# Sheet1.net
KiCad netlist of a schematic drawn in Altium Designer
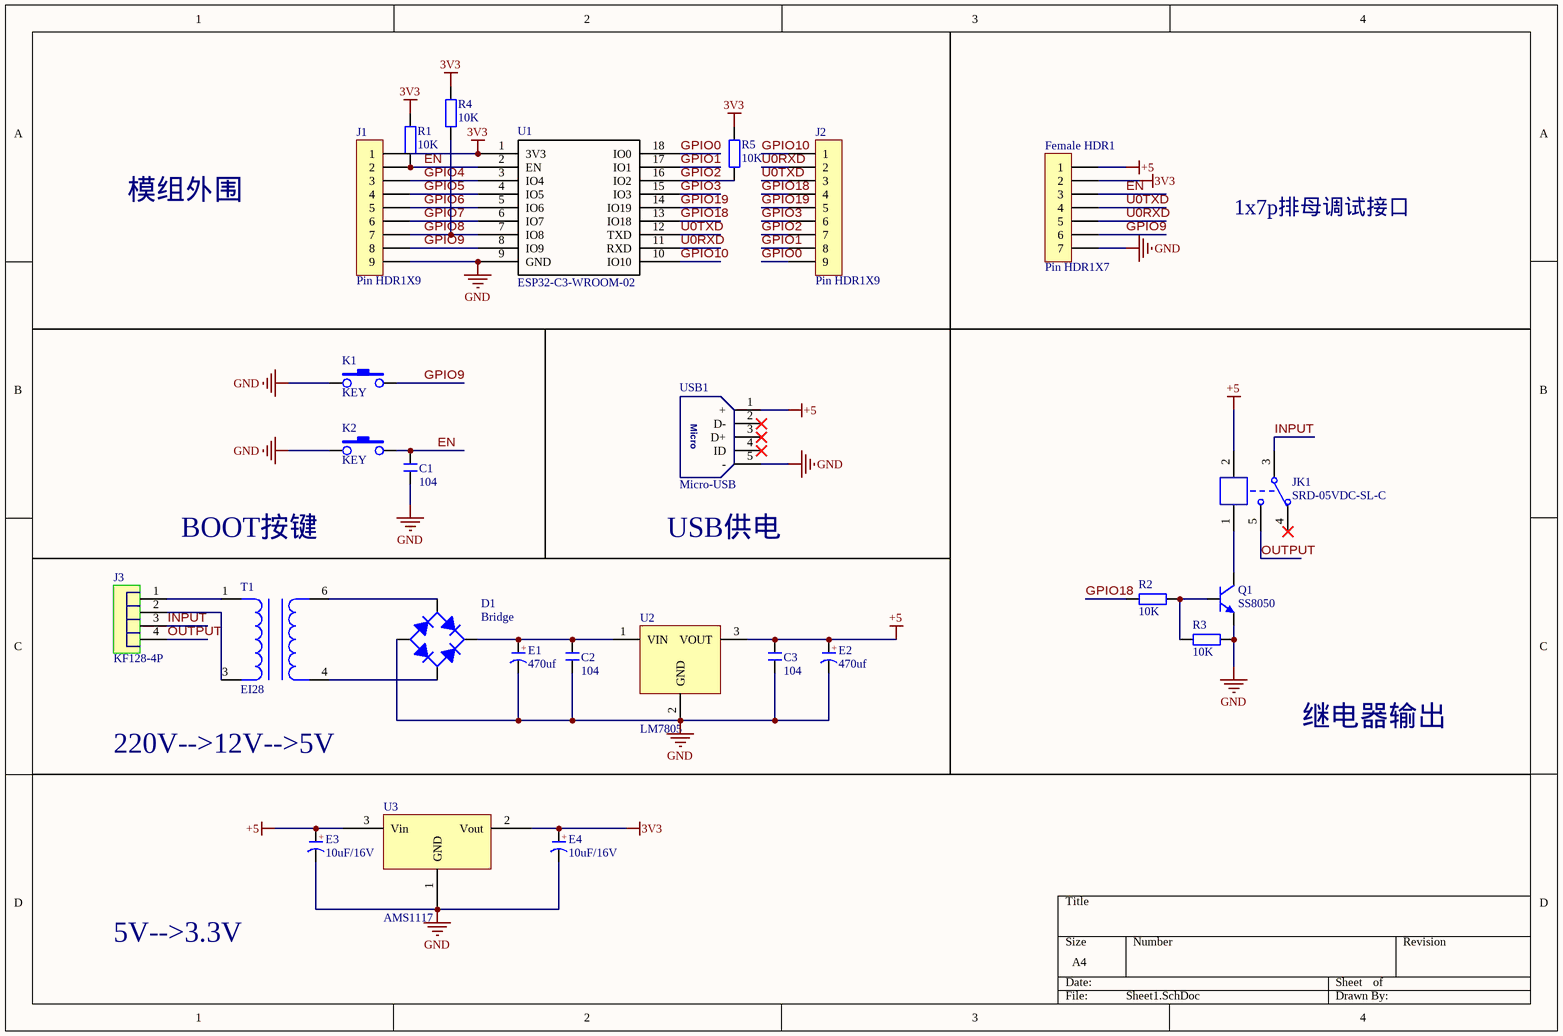
[diagram p0: Sheet1.SchDoc]

(export (version "E")
  (design (tool "Eeschema 10.0.6"))
  (components
    (comp (ref "C1")
      (value "104")
      (footprint "CC 1.8*3.6")
      (description "直插瓷片电容")
      (fields (field (name "版权归属") "源创客"))
      (libsource (lib "3.1   - 电阻-电容-电感") (part "C-CC"))
    )
    (comp (ref "C2")
      (value "104")
      (footprint "CC 1.8*3.6")
      (description "直插瓷片电容")
      (fields (field (name "版权归属") "源创客"))
      (libsource (lib "3.1   - 电阻-电容-电感") (part "C-CC"))
    )
    (comp (ref "C3")
      (value "104")
      (footprint "CC 1.8*3.6")
      (description "直插瓷片电容")
      (fields (field (name "版权归属") "源创客"))
      (libsource (lib "3.1   - 电阻-电容-电感") (part "C-CC"))
    )
    (comp (ref "D1") (value "Bridge") (footprint "GBP") (libsource (lib "IOT_light") (part "Bridge")))
    (comp (ref "E1")
      (value "470uf")
      (footprint "CAP 1.5*4*8")
      (description "直插电解电容")
      (fields (field (name "版权归属") "源创客"))
      (libsource (lib "3.1   - 电阻-电容-电感") (part "C-CAP"))
    )
    (comp (ref "E2")
      (value "470uf")
      (footprint "CAP 1.5*4*8")
      (description "直插电解电容")
      (fields (field (name "版权归属") "源创客"))
      (libsource (lib "3.1   - 电阻-电容-电感") (part "C-CAP"))
    )
    (comp (ref "E3")
      (value "10uF/16V")
      (footprint "CAP 1.5*4*8")
      (description "直插电解电容")
      (fields (field (name "版权归属") "源创客"))
      (libsource (lib "3.1   - 电阻-电容-电感") (part "C-CAP"))
    )
    (comp (ref "E4")
      (value "10uF/16V")
      (footprint "CAP 1.5*4*8")
      (description "直插电解电容")
      (fields (field (name "版权归属") "源创客"))
      (libsource (lib "3.1   - 电阻-电容-电感") (part "C-CAP"))
    )
    (comp (ref "Female HDR1")
      (value "Pin HDR1X7")
      (footprint "Pin HDR1X7/2.54mm-W")
      (libsource (lib "IOT_light") (part "Pin HDR1X7"))
    )
    (comp (ref "J1")
      (value "Pin HDR1X9")
      (footprint "Pin HDR1X9/2.54mm-W")
      (libsource (lib "") (part "Pin HDR1X9_1"))
    )
    (comp (ref "J2")
      (value "Pin HDR1X9")
      (footprint "Pin HDR1X9/2.54mm-W")
      (libsource (lib "IOT_light") (part "Pin HDR1X9"))
    )
    (comp (ref "J3")
      (value "KF128-4P")
      (footprint "KF128-3.81-4P")
      (libsource (lib "KF128") (part "KF128-4P"))
    )
    (comp (ref "JK1")
      (value "SRD-05VDC-SL-C")
      (footprint "SRD-C_B")
      (description "5V一组转换")
      (libsource (lib "继电器") (part "SRD-05VDC-SL-C"))
    )
    (comp (ref "K1") (value "KEY") (footprint "DIP-3X6X4.3") (libsource (lib "IOT_light") (part "KEY")))
    (comp (ref "K2") (value "KEY") (footprint "DIP-3X6X4.3") (libsource (lib "IOT_light") (part "KEY")))
    (comp (ref "Q1")
      (value "SS8050")
      (footprint "SOT23-3N")
      (description "高频放大-NPN型")
      (fields (field (name "版权归属") "源创客"))
      (libsource (lib "6.2   - 三极管") (part "8050-SMD"))
    )
    (comp (ref "R1")
      (value "10K")
      (footprint "RS 1/4W")
      (description "直插色环电阻")
      (fields (field (name "版权归属") "源创客"))
      (libsource (lib "3.1   - 电阻-电容-电感") (part "R-CRR"))
    )
    (comp (ref "R2")
      (value "10K")
      (footprint "RS 1/4W")
      (description "直插色环电阻")
      (fields (field (name "版权归属") "源创客"))
      (libsource (lib "3.1   - 电阻-电容-电感") (part "R-CRR"))
    )
    (comp (ref "R3")
      (value "10K")
      (footprint "RS 1/4W")
      (description "直插色环电阻")
      (fields (field (name "版权归属") "源创客"))
      (libsource (lib "3.1   - 电阻-电容-电感") (part "R-CRR"))
    )
    (comp (ref "R4")
      (value "10K")
      (footprint "RS 1/4W")
      (description "直插色环电阻")
      (fields (field (name "版权归属") "源创客"))
      (libsource (lib "3.1   - 电阻-电容-电感") (part "R-CRR"))
    )
    (comp (ref "R5")
      (value "10K")
      (footprint "RS 1/4W")
      (description "直插色环电阻")
      (fields (field (name "版权归属") "源创客"))
      (libsource (lib "3.1   - 电阻-电容-电感") (part "R-CRR"))
    )
    (comp (ref "T1")
      (value "EI28")
      (footprint "DA10XC")
      (description "EI28卧式1.2W220V转12V工频PCB线路板直插针式小型变压器单相交流")
      (fields (field (name "版权归属") "源创客"))
      (libsource (lib "12.1 - 变压器") (part "DA10XC"))
    )
    (comp (ref "U1")
      (value "ESP32­C3­WROOM­02")
      (footprint "ESP32C3")
      (description "ESP32-C3模块")
      (libsource (lib "ESP32C3_Smart_lights") (part "ESP32­C3­WROOM­02"))
    )
    (comp (ref "U2") (value "LM7805") (footprint "TO220A") (libsource (lib "电源芯片") (part "LM7805")))
    (comp (ref "U3")
      (value "AMS1117")
      (footprint "SOT223")
      (description "三端稳压芯片")
      (libsource (lib "电源芯片") (part "AMS1117"))
    )
    (comp (ref "USB1")
      (value "Micro-USB")
      (footprint "USB-MICRO_A")
      (libsource (lib "USB") (part "Micro-USB"))
    )
  )
  (nets
    (net (code "1") (name "+5") (class "Default")
      (node (ref "C3") (pin "1") (pinfunction "1_1") (pintype "passive"))
      (node (ref "E2") (pin "1") (pinfunction "A_1") (pintype "passive"))
      (node (ref "E3") (pin "1") (pinfunction "A_1") (pintype "passive"))
      (node (ref "Female HDR1") (pin "1") (pinfunction "1_1") (pintype "passive"))
      (node (ref "JK1") (pin "2") (pinfunction "2_2") (pintype "passive"))
      (node (ref "U2") (pin "3") (pinfunction "VOUT_3") (pintype "passive"))
      (node (ref "U3") (pin "3") (pinfunction "Vin_3") (pintype "passive"))
      (node (ref "USB1") (pin "1") (pinfunction "+_1") (pintype "passive"))
    )
    (net (code "2") (name "/EN") (class "Default")
      (node (ref "C1") (pin "1") (pinfunction "1_1") (pintype "passive"))
      (node (ref "Female HDR1") (pin "3") (pinfunction "3_3") (pintype "passive"))
      (node (ref "J1") (pin "2") (pinfunction "2_2") (pintype "passive"))
      (node (ref "K2") (pin "3") (pinfunction "3_3") (pintype "passive"))
      (node (ref "R1") (pin "1") (pinfunction "1_1") (pintype "passive"))
      (node (ref "U1") (pin "2") (pinfunction "EN_2") (pintype "passive"))
    )
    (net (code "3") (name "/GPIO0") (class "Default")
      (node (ref "J2") (pin "9") (pinfunction "9_9") (pintype "passive"))
      (node (ref "U1") (pin "18") (pinfunction "IO0_18") (pintype "passive"))
    )
    (net (code "4") (name "/GPIO1") (class "Default")
      (node (ref "J2") (pin "8") (pinfunction "8_8") (pintype "passive"))
      (node (ref "U1") (pin "17") (pinfunction "IO1_17") (pintype "passive"))
    )
    (net (code "5") (name "/GPIO2") (class "Default")
      (node (ref "J2") (pin "7") (pinfunction "7_7") (pintype "passive"))
      (node (ref "R5") (pin "1") (pinfunction "1_1") (pintype "passive"))
      (node (ref "U1") (pin "16") (pinfunction "IO2_16") (pintype "passive"))
    )
    (net (code "6") (name "/GPIO3") (class "Default")
      (node (ref "J2") (pin "6") (pinfunction "6_6") (pintype "passive"))
      (node (ref "U1") (pin "15") (pinfunction "IO3_15") (pintype "passive"))
    )
    (net (code "7") (name "/GPIO4") (class "Default")
      (node (ref "J1") (pin "3") (pinfunction "3_3") (pintype "passive"))
      (node (ref "U1") (pin "3") (pinfunction "IO4_3") (pintype "passive"))
    )
    (net (code "8") (name "/GPIO5") (class "Default")
      (node (ref "J1") (pin "4") (pinfunction "4_4") (pintype "passive"))
      (node (ref "U1") (pin "4") (pinfunction "IO5_4") (pintype "passive"))
    )
    (net (code "9") (name "/GPIO6") (class "Default")
      (node (ref "J1") (pin "5") (pinfunction "5_5") (pintype "passive"))
      (node (ref "U1") (pin "5") (pinfunction "IO6_5") (pintype "passive"))
    )
    (net (code "10") (name "/GPIO7") (class "Default")
      (node (ref "J1") (pin "6") (pinfunction "6_6") (pintype "passive"))
      (node (ref "U1") (pin "6") (pinfunction "IO7_6") (pintype "passive"))
    )
    (net (code "11") (name "/GPIO8") (class "Default")
      (node (ref "J1") (pin "7") (pinfunction "7_7") (pintype "passive"))
      (node (ref "R4") (pin "1") (pinfunction "1_1") (pintype "passive"))
      (node (ref "U1") (pin "7") (pinfunction "IO8_7") (pintype "passive"))
    )
    (net (code "12") (name "/GPIO9") (class "Default")
      (node (ref "Female HDR1") (pin "6") (pinfunction "6_6") (pintype "passive"))
      (node (ref "J1") (pin "8") (pinfunction "8_8") (pintype "passive"))
      (node (ref "K1") (pin "3") (pinfunction "3_3") (pintype "passive"))
      (node (ref "U1") (pin "8") (pinfunction "IO9_8") (pintype "passive"))
    )
    (net (code "13") (name "/GPIO10") (class "Default")
      (node (ref "J2") (pin "1") (pinfunction "1_1") (pintype "passive"))
      (node (ref "U1") (pin "10") (pinfunction "IO10_10") (pintype "passive"))
    )
    (net (code "14") (name "/GPIO18") (class "Default")
      (node (ref "J2") (pin "4") (pinfunction "4_4") (pintype "passive"))
      (node (ref "R2") (pin "1") (pinfunction "1_1") (pintype "passive"))
      (node (ref "U1") (pin "13") (pinfunction "IO18_13") (pintype "passive"))
    )
    (net (code "15") (name "/GPIO19") (class "Default")
      (node (ref "J2") (pin "5") (pinfunction "5_5") (pintype "passive"))
      (node (ref "U1") (pin "14") (pinfunction "IO19_14") (pintype "passive"))
    )
    (net (code "16") (name "/INPUT") (class "Default")
      (node (ref "J3") (pin "3") (pinfunction "3_3") (pintype "passive"))
      (node (ref "JK1") (pin "3") (pinfunction "3_3") (pintype "passive"))
    )
    (net (code "17") (name "/OUTPUT") (class "Default")
      (node (ref "J3") (pin "4") (pinfunction "4_4") (pintype "passive"))
      (node (ref "JK1") (pin "5") (pinfunction "5_5") (pintype "passive"))
    )
    (net (code "18") (name "/U0RXD") (class "Default")
      (node (ref "Female HDR1") (pin "5") (pinfunction "5_5") (pintype "passive"))
      (node (ref "J2") (pin "2") (pinfunction "2_2") (pintype "passive"))
      (node (ref "U1") (pin "11") (pinfunction "RXD_11") (pintype "passive"))
    )
    (net (code "19") (name "/U0TXD") (class "Default")
      (node (ref "Female HDR1") (pin "4") (pinfunction "4_4") (pintype "passive"))
      (node (ref "J2") (pin "3") (pinfunction "3_3") (pintype "passive"))
      (node (ref "U1") (pin "12") (pinfunction "TXD_12") (pintype "passive"))
    )
    (net (code "20") (name "3V3") (class "Default")
      (node (ref "E4") (pin "1") (pinfunction "A_1") (pintype "passive"))
      (node (ref "Female HDR1") (pin "2") (pinfunction "2_2") (pintype "passive"))
      (node (ref "J1") (pin "1") (pinfunction "1_1") (pintype "passive"))
      (node (ref "R1") (pin "2") (pinfunction "2_2") (pintype "passive"))
      (node (ref "R4") (pin "2") (pinfunction "2_2") (pintype "passive"))
      (node (ref "R5") (pin "2") (pinfunction "2_2") (pintype "passive"))
      (node (ref "U1") (pin "1") (pinfunction "3V3_1") (pintype "passive"))
      (node (ref "U3") (pin "2") (pinfunction "Vout_2") (pintype "passive"))
    )
    (net (code "21") (name "GND") (class "Default")
      (node (ref "C1") (pin "2") (pinfunction "2_2") (pintype "passive"))
      (node (ref "C2") (pin "2") (pinfunction "2_2") (pintype "passive"))
      (node (ref "C3") (pin "2") (pinfunction "2_2") (pintype "passive"))
      (node (ref "D1") (pin "DC-") (pinfunction "DC-_DC-") (pintype "passive"))
      (node (ref "E1") (pin "2") (pinfunction "K_2") (pintype "passive"))
      (node (ref "E2") (pin "2") (pinfunction "K_2") (pintype "passive"))
      (node (ref "E3") (pin "2") (pinfunction "K_2") (pintype "passive"))
      (node (ref "E4") (pin "2") (pinfunction "K_2") (pintype "passive"))
      (node (ref "Female HDR1") (pin "7") (pinfunction "7_7") (pintype "passive"))
      (node (ref "J1") (pin "9") (pinfunction "9_9") (pintype "passive"))
      (node (ref "K1") (pin "1") (pinfunction "1_1") (pintype "passive"))
      (node (ref "K2") (pin "1") (pinfunction "1_1") (pintype "passive"))
      (node (ref "Q1") (pin "2") (pinfunction "E_2") (pintype "passive"))
      (node (ref "R3") (pin "2") (pinfunction "2_2") (pintype "passive"))
      (node (ref "U1") (pin "9") (pinfunction "GND_9") (pintype "passive"))
      (node (ref "U2") (pin "2") (pinfunction "GND_2") (pintype "passive"))
      (node (ref "U3") (pin "1") (pinfunction "GND_1") (pintype "passive"))
      (node (ref "USB1") (pin "5") (pinfunction "-_5") (pintype "passive"))
    )
    (net (code "22") (name "Net-(D1-PadAC1)") (class "Default")
      (node (ref "D1") (pin "AC1") (pinfunction "AC1_AC1") (pintype "passive"))
      (node (ref "T1") (pin "6") (pinfunction "6_6") (pintype "passive"))
    )
    (net (code "23") (name "Net-(D1-PadAC2)") (class "Default")
      (node (ref "D1") (pin "AC2") (pinfunction "AC2_AC2") (pintype "passive"))
      (node (ref "T1") (pin "4") (pinfunction "4_4") (pintype "passive"))
    )
    (net (code "24") (name "Net-(E1-A)") (class "Default")
      (node (ref "C2") (pin "1") (pinfunction "1_1") (pintype "passive"))
      (node (ref "D1") (pin "DC+") (pinfunction "DC+_DC+") (pintype "passive"))
      (node (ref "E1") (pin "1") (pinfunction "A_1") (pintype "passive"))
      (node (ref "U2") (pin "1") (pinfunction "VIN_1") (pintype "passive"))
    )
    (net (code "25") (name "Net-(J3-Pad1)") (class "Default")
      (node (ref "J3") (pin "1") (pinfunction "1_1") (pintype "passive"))
      (node (ref "T1") (pin "1") (pinfunction "1_1") (pintype "passive"))
    )
    (net (code "26") (name "Net-(J3-Pad2)") (class "Default")
      (node (ref "J3") (pin "2") (pinfunction "2_2") (pintype "passive"))
      (node (ref "T1") (pin "3") (pinfunction "3_3") (pintype "passive"))
    )
    (net (code "27") (name "Net-(Q1-B)") (class "Default")
      (node (ref "Q1") (pin "1") (pinfunction "B_1") (pintype "passive"))
      (node (ref "R2") (pin "2") (pinfunction "2_2") (pintype "passive"))
      (node (ref "R3") (pin "1") (pinfunction "1_1") (pintype "passive"))
    )
    (net (code "28") (name "Net-(Q1-C)") (class "Default")
      (node (ref "JK1") (pin "1") (pinfunction "1_1") (pintype "passive"))
      (node (ref "Q1") (pin "3") (pinfunction "C_3") (pintype "passive"))
    )
    (net (code "29") (name "unconnected-(JK1-Pad4)") (class "Default")
      (node (ref "JK1") (pin "4") (pinfunction "4_4") (pintype "passive+no_connect"))
    )
    (net (code "30") (name "unconnected-(USB1-D+-Pad3)") (class "Default")
      (node (ref "USB1") (pin "3") (pinfunction "D+_3") (pintype "passive+no_connect"))
    )
    (net (code "31") (name "unconnected-(USB1-D--Pad2)") (class "Default")
      (node (ref "USB1") (pin "2") (pinfunction "D-_2") (pintype "passive+no_connect"))
    )
    (net (code "32") (name "unconnected-(USB1-ID-Pad4)") (class "Default")
      (node (ref "USB1") (pin "4") (pinfunction "ID_4") (pintype "passive+no_connect"))
    )
  )
)
